# Microcontroller_schematic.net
KiCad netlist of a schematic drawn in Altium Designer
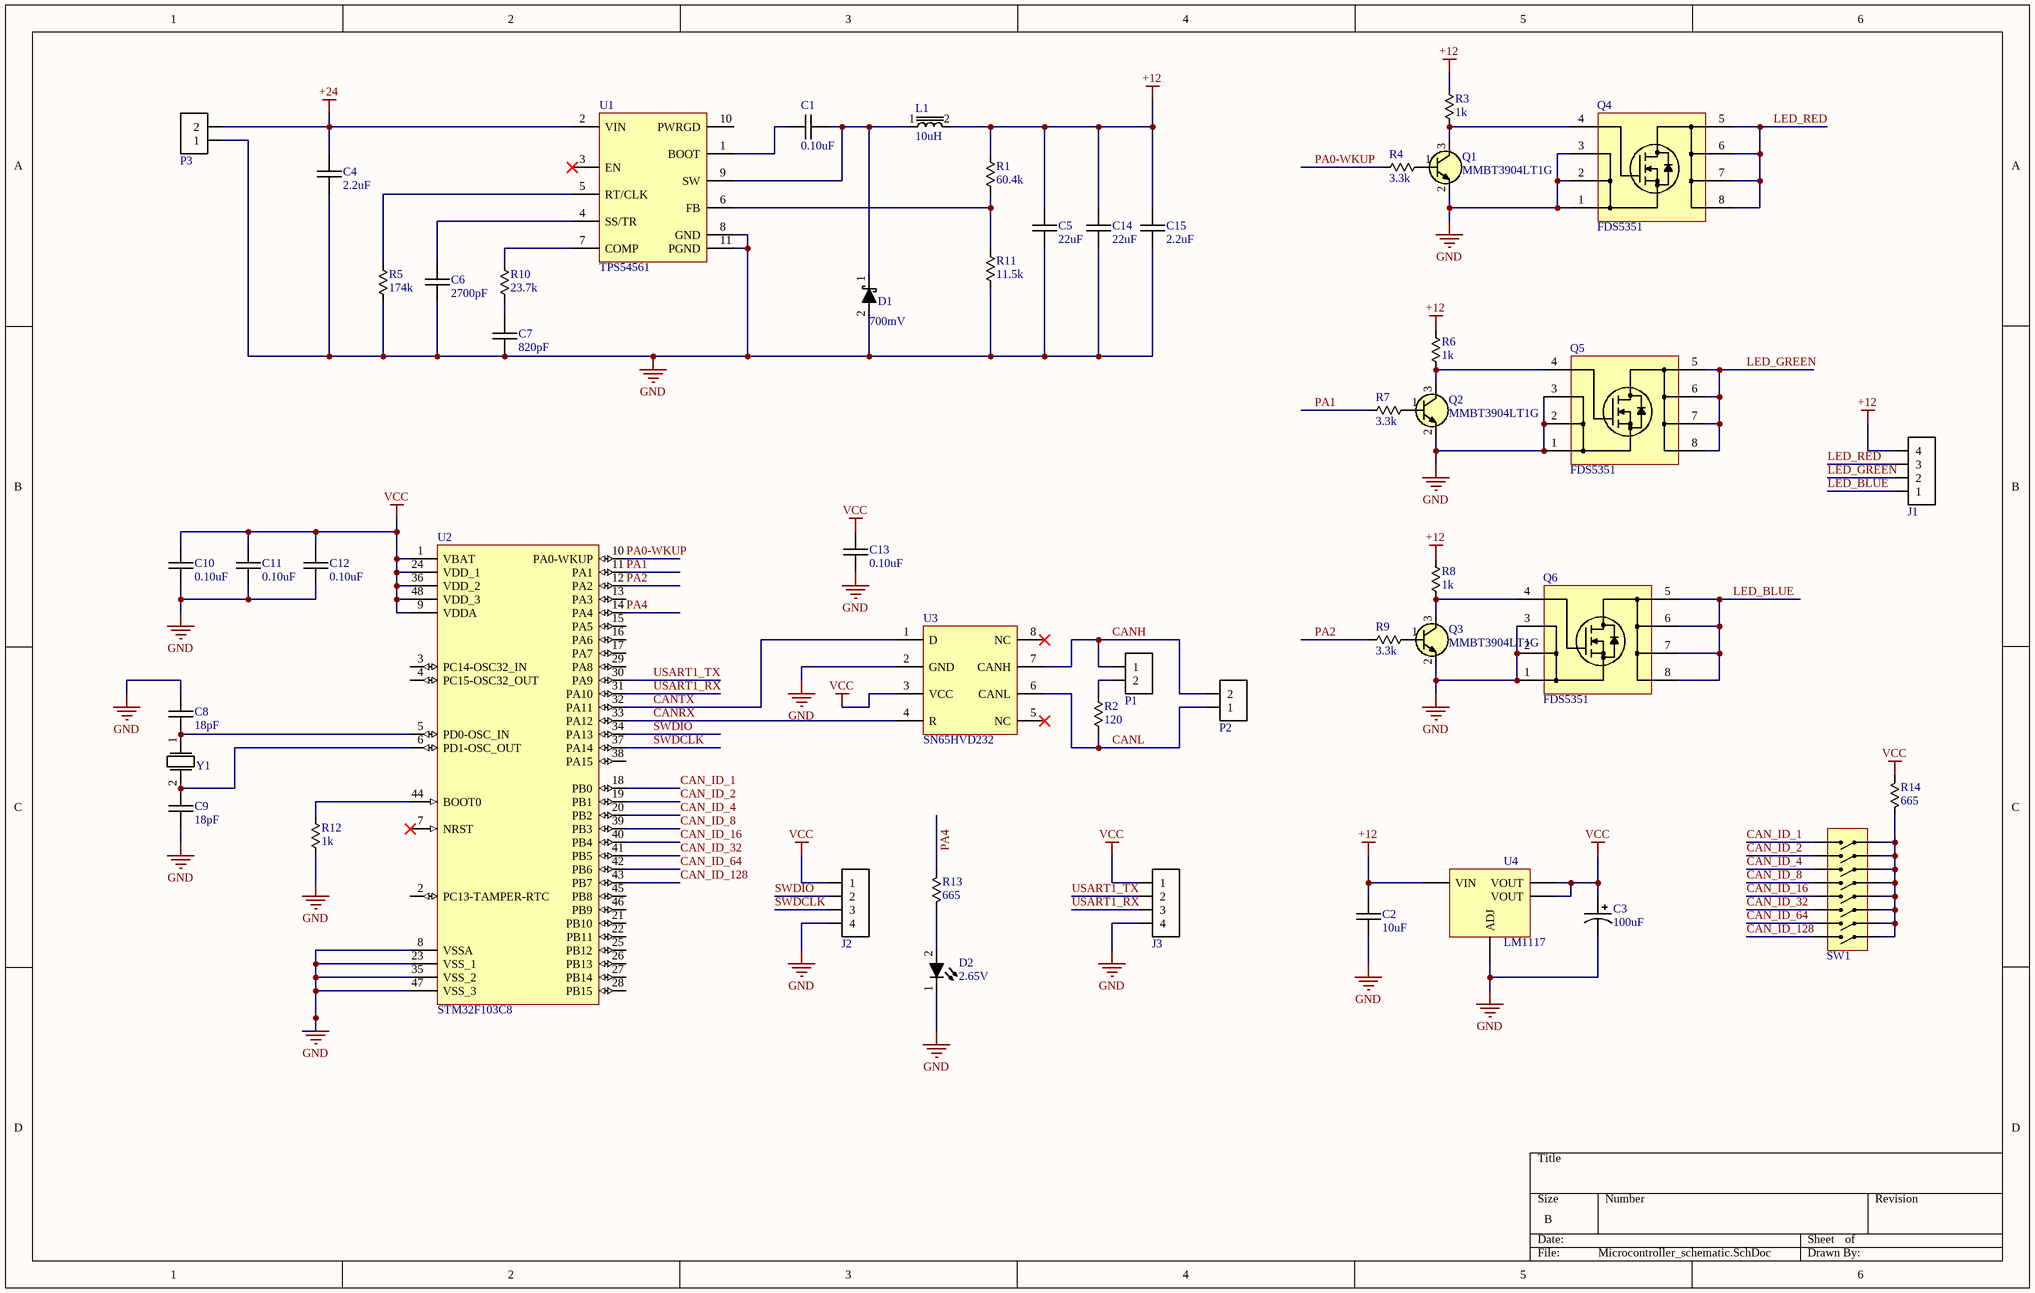
[diagram p0: Microcontroller_schematic.SchDoc]

(export (version "E")
  (design (tool "Eeschema 10.0.6"))
  (components
    (comp (ref "C1")
      (value "0.10uF")
      (footprint "chip_0805")
      (description "CAP, 0.10uF, 10%, 16V, X7R, 0805")
      (fields (field (name "PART NUMBER") "CAP-00069") (field (name "TOLERANCE") "10%"))
      (libsource (lib "Capacitors$") (part "CAP-00069"))
    )
    (comp (ref "C2")
      (value "10uF")
      (footprint "chip_1206")
      (description "CAP, 10uF, ±10%, 25V, X7R, 1206")
      (fields (field (name "PART NUMBER") "CAP-00539") (field (name "TOLERANCE") "±10%"))
      (libsource (lib "Capacitors$") (part "CAP-00539"))
    )
    (comp (ref "C3")
      (value "100uF")
      (footprint "chip_2917_AVX_TAJD")
      (description "CAP, 100uF, ±10%, 16V, Tantalum, 2917")
      (fields (field (name "PART NUMBER") "CAP-00550") (field (name "TOLERANCE") "±10%"))
      (libsource (lib "Capacitors$") (part "CAP-00550"))
    )
    (comp (ref "C4")
      (value "2.2uF")
      (footprint "chip_1206")
      (description "CAP, 2.2uF, ±10%, 50V, X7R, 1206")
      (fields (field (name "PART NUMBER") "CAP-00563") (field (name "TOLERANCE") "±10%"))
      (libsource (lib "Capacitors$") (part "CAP-00563"))
    )
    (comp (ref "C5")
      (value "22uF")
      (footprint "chip_1206")
      (description "CAP, 22uF, ±10%, 25V, X5R, 1206")
      (fields (field (name "PART NUMBER") "CAP-00587") (field (name "TOLERANCE") "±10%"))
      (libsource (lib "Capacitors$") (part "CAP-00587"))
    )
    (comp (ref "C6")
      (value "2700pF")
      (footprint "chip_0805")
      (description "CAP, 2700pF, 10%, 50V, X7R, 0805")
      (fields (field (name "PART NUMBER") "CAP-00024") (field (name "TOLERANCE") "10%"))
      (libsource (lib "Capacitors$") (part "CAP-00024"))
    )
    (comp (ref "C7")
      (value "820pF")
      (footprint "chip_0805")
      (description "CAP, 820pF, 10%, 50V, X7R, 0805")
      (fields (field (name "PART NUMBER") "CAP-00008") (field (name "TOLERANCE") "10%"))
      (libsource (lib "Capacitors$") (part "CAP-00008"))
    )
    (comp (ref "C8")
      (value "18pF")
      (footprint "chip_0603")
      (description "CAP, 18pF, ±2%, 50V, C0G, 0603")
      (fields (field (name "PART NUMBER") "CAP-00409") (field (name "TOLERANCE") "±2%"))
      (libsource (lib "Capacitors$") (part "CAP-00409"))
    )
    (comp (ref "C9")
      (value "18pF")
      (footprint "chip_0603")
      (description "CAP, 18pF, ±2%, 50V, C0G, 0603")
      (fields (field (name "PART NUMBER") "CAP-00409") (field (name "TOLERANCE") "±2%"))
      (libsource (lib "Capacitors$") (part "CAP-00409"))
    )
    (comp (ref "C10")
      (value "0.10uF")
      (footprint "chip_0805")
      (description "CAP, 0.10uF, 10%, 16V, X7R, 0805")
      (fields (field (name "PART NUMBER") "CAP-00069") (field (name "TOLERANCE") "10%"))
      (libsource (lib "Capacitors$") (part "CAP-00069"))
    )
    (comp (ref "C11")
      (value "0.10uF")
      (footprint "chip_0805")
      (description "CAP, 0.10uF, 10%, 16V, X7R, 0805")
      (fields (field (name "PART NUMBER") "CAP-00069") (field (name "TOLERANCE") "10%"))
      (libsource (lib "Capacitors$") (part "CAP-00069"))
    )
    (comp (ref "C12")
      (value "0.10uF")
      (footprint "chip_0805")
      (description "CAP, 0.10uF, 10%, 16V, X7R, 0805")
      (fields (field (name "PART NUMBER") "CAP-00069") (field (name "TOLERANCE") "10%"))
      (libsource (lib "Capacitors$") (part "CAP-00069"))
    )
    (comp (ref "C13")
      (value "0.10uF")
      (footprint "chip_0805")
      (description "CAP, 0.10uF, 10%, 16V, X7R, 0805")
      (fields (field (name "PART NUMBER") "CAP-00069") (field (name "TOLERANCE") "10%"))
      (libsource (lib "Capacitors$") (part "CAP-00069"))
    )
    (comp (ref "C14")
      (value "22uF")
      (footprint "chip_1206")
      (description "CAP, 22uF, ±10%, 25V, X5R, 1206")
      (fields (field (name "PART NUMBER") "CAP-00587") (field (name "TOLERANCE") "±10%"))
      (libsource (lib "Capacitors$") (part "CAP-00587"))
    )
    (comp (ref "C15")
      (value "2.2uF")
      (footprint "chip_1206")
      (description "CAP, 2.2uF, ±10%, 50V, X7R, 1206")
      (fields (field (name "PART NUMBER") "CAP-00563") (field (name "TOLERANCE") "±10%"))
      (libsource (lib "Capacitors$") (part "CAP-00563"))
    )
    (comp (ref "D1")
      (value "700mV")
      (footprint "do-214ab")
      (description "Dio, Schottky, 5A, 700mV, 60V, SMC")
      (fields (field (name "PART NUMBER") "DIO-00048") (field (name "MANUFACTURER") "Diodes Incorporated"))
      (libsource (lib "Diodes$") (part "DIO-00048"))
    )
    (comp (ref "D2")
      (value "2.65V")
      (footprint "chip_0603_LED")
      (description "LED, Green, 0603, Low current, HELI2 Series")
      (fields (field (name "PART NUMBER") "DIO-00050") (field (name "MANUFACTURER") "Kingbright"))
      (libsource (lib "Diodes$") (part "DIO-00050"))
    )
    (comp (ref "J1")
      (value "conn-4x1_0")
      (footprint "TERM_3.50MM_4x1_0")
      (description "Term Blk, 4 Pos, 8A, 3.5mm Pitch, Screwless")
      (fields (field (name "PART NUMBER") "CONN-00024") (field (name "MANUFACTURER") "Phoenix Contact"))
      (libsource (lib "Connectors$") (part "CONN-00024"))
    )
    (comp (ref "J2")
      (value "conn-4x1_0")
      (footprint "HDDR_4x1_0")
      (description "Header 4x1, 0.1\"")
      (fields (field (name "PART NUMBER") "CONN-00029"))
      (libsource (lib "Connectors$") (part "CONN-00029"))
    )
    (comp (ref "J3")
      (value "conn-4x1_0")
      (footprint "HDDR_4x1_0")
      (description "Header 4x1, 0.1\"")
      (fields (field (name "PART NUMBER") "CONN-00029"))
      (libsource (lib "Connectors$") (part "CONN-00029"))
    )
    (comp (ref "L1")
      (value "ind_1")
      (footprint "VISHAY_IHLP3232DZ")
      (description "Ind, 10uH, 20%, 5.2A (9A sat.), 0.0599 Ohm")
      (fields
        (field (name "PART NUMBER") "MAG-00106")
        (field (name "INDUCTANCE") "10uH")
        (field (name "TOLERANCE") "20%")
      )
      (libsource (lib "Magnetics$") (part "MAG-00106"))
    )
    (comp (ref "P1")
      (value "conn-2x1_0")
      (footprint "HDDR_2x1_0")
      (description "Header, 2x1, 0.1\"")
      (fields (field (name "PART NUMBER") "CONN-00055") (field (name "MANUFACTURER") "Samtec"))
      (libsource (lib "Connectors$") (part "CONN-00055"))
    )
    (comp (ref "P2")
      (value "conn-2x1_0")
      (footprint "TERM_3.50MM_2x1_0")
      (description "Term Blk, 2 Pos, 8A, 3.5mm Pitch, Screwless")
      (fields (field (name "PART NUMBER") "CONN-00023") (field (name "MANUFACTURER") "Phoenix Contact"))
      (libsource (lib "Connectors$") (part "CONN-00023"))
    )
    (comp (ref "P3")
      (value "conn-2x1_0")
      (footprint "TERM_3.50MM_2x1_0")
      (description "Term Blk, 2 Pos, 8A, 3.5mm Pitch, Screwless")
      (fields (field (name "PART NUMBER") "CONN-00023") (field (name "MANUFACTURER") "Phoenix Contact"))
      (libsource (lib "Connectors$") (part "CONN-00023"))
    )
    (comp (ref "Q1")
      (value "MMBT3904LT1G")
      (footprint "SOT-23-3_1")
      (description "XSTR, NPN, 200mA, 40V, Vce 0.3V, SOT-23-3")
      (fields (field (name "PART NUMBER") "XSTR-00037") (field (name "MANUFACTURER") "ON Semi"))
      (libsource (lib "Transistors$") (part "XSTR-00037"))
    )
    (comp (ref "Q2")
      (value "MMBT3904LT1G")
      (footprint "SOT-23-3_1")
      (description "XSTR, NPN, 200mA, 40V, Vce 0.3V, SOT-23-3")
      (fields (field (name "PART NUMBER") "XSTR-00037") (field (name "MANUFACTURER") "ON Semi"))
      (libsource (lib "Transistors$") (part "XSTR-00037"))
    )
    (comp (ref "Q3")
      (value "MMBT3904LT1G")
      (footprint "SOT-23-3_1")
      (description "XSTR, NPN, 200mA, 40V, Vce 0.3V, SOT-23-3")
      (fields (field (name "PART NUMBER") "XSTR-00037") (field (name "MANUFACTURER") "ON Semi"))
      (libsource (lib "Transistors$") (part "XSTR-00037"))
    )
    (comp (ref "Q4")
      (value "FDS5351")
      (footprint "SO-8")
      (description "XSTR NFET, 6.1A, 60V, 5W, SOIC-8")
      (fields (field (name "PART NUMBER") "XSTR-00034") (field (name "MANUFACTURER") "ON Semi"))
      (libsource (lib "Transistors$") (part "XSTR-00034"))
    )
    (comp (ref "Q5")
      (value "FDS5351")
      (footprint "SO-8")
      (description "XSTR NFET, 6.1A, 60V, 5W, SOIC-8")
      (fields (field (name "PART NUMBER") "XSTR-00034") (field (name "MANUFACTURER") "ON Semi"))
      (libsource (lib "Transistors$") (part "XSTR-00034"))
    )
    (comp (ref "Q6")
      (value "FDS5351")
      (footprint "SO-8")
      (description "XSTR NFET, 6.1A, 60V, 5W, SOIC-8")
      (fields (field (name "PART NUMBER") "XSTR-00034") (field (name "MANUFACTURER") "ON Semi"))
      (libsource (lib "Transistors$") (part "XSTR-00034"))
    )
    (comp (ref "R1")
      (value "60.4k")
      (footprint "chip_0805")
      (description "RES SMD 60.4K OHM 1% 1/8W 0805")
      (fields (field (name "PART NUMBER") "RES-00531") (field (name "TOLERANCE") "1%"))
      (libsource (lib "Resistors$") (part "RES-00531"))
    )
    (comp (ref "R2")
      (value "120")
      (footprint "chip_0805")
      (description "RES SMD 120 OHM 1% 1/8W 0805")
      (fields (field (name "PART NUMBER") "RES-00183") (field (name "TOLERANCE") "1%"))
      (libsource (lib "Resistors$") (part "RES-00183"))
    )
    (comp (ref "R3")
      (value "1k")
      (footprint "chip_0805")
      (description "RES SMD 1K OHM 1% 1/8W 0805")
      (fields (field (name "PART NUMBER") "RES-00361") (field (name "TOLERANCE") "1%"))
      (libsource (lib "Resistors$") (part "RES-00361"))
    )
    (comp (ref "R4")
      (value "3.3k")
      (footprint "chip_0603")
      (description "RES SMD 3.3K OHM 1% 1/4W 0603")
      (fields (field (name "PART NUMBER") "RES-00419") (field (name "TOLERANCE") "1%"))
      (libsource (lib "Resistors$") (part "RES-00419"))
    )
    (comp (ref "R5")
      (value "174k")
      (footprint "chip_0805")
      (description "RES SMD 174K OHM 1% 1/8W 0805")
      (fields (field (name "PART NUMBER") "RES-00350") (field (name "TOLERANCE") "1%"))
      (libsource (lib "Resistors$") (part "RES-00350"))
    )
    (comp (ref "R6")
      (value "1k")
      (footprint "chip_0805")
      (description "RES SMD 1K OHM 1% 1/8W 0805")
      (fields (field (name "PART NUMBER") "RES-00361") (field (name "TOLERANCE") "1%"))
      (libsource (lib "Resistors$") (part "RES-00361"))
    )
    (comp (ref "R7")
      (value "3.3k")
      (footprint "chip_0603")
      (description "RES SMD 3.3K OHM 1% 1/4W 0603")
      (fields (field (name "PART NUMBER") "RES-00419") (field (name "TOLERANCE") "1%"))
      (libsource (lib "Resistors$") (part "RES-00419"))
    )
    (comp (ref "R8")
      (value "1k")
      (footprint "chip_0805")
      (description "RES SMD 1K OHM 1% 1/8W 0805")
      (fields (field (name "PART NUMBER") "RES-00361") (field (name "TOLERANCE") "1%"))
      (libsource (lib "Resistors$") (part "RES-00361"))
    )
    (comp (ref "R9")
      (value "3.3k")
      (footprint "chip_0603")
      (description "RES SMD 3.3K OHM 1% 1/4W 0603")
      (fields (field (name "PART NUMBER") "RES-00419") (field (name "TOLERANCE") "1%"))
      (libsource (lib "Resistors$") (part "RES-00419"))
    )
    (comp (ref "R10")
      (value "23.7k")
      (footprint "chip_0805")
      (description "RES SMD 23.7K OHM 1% 1/8W 0805")
      (fields (field (name "PART NUMBER") "RES-00392") (field (name "TOLERANCE") "1%"))
      (libsource (lib "Resistors$") (part "RES-00392"))
    )
    (comp (ref "R11")
      (value "11.5k")
      (footprint "chip_0805")
      (description "RES SMD 11.5K OHM 1% 1/8W 0805")
      (fields (field (name "PART NUMBER") "RES-00309") (field (name "TOLERANCE") "1%"))
      (libsource (lib "Resistors$") (part "RES-00309"))
    )
    (comp (ref "R12")
      (value "1k")
      (footprint "chip_0805")
      (description "RES SMD 1K OHM 1% 1/8W 0805")
      (fields (field (name "PART NUMBER") "RES-00361") (field (name "TOLERANCE") "1%"))
      (libsource (lib "Resistors$") (part "RES-00361"))
    )
    (comp (ref "R13")
      (value "665")
      (footprint "chip_0805")
      (description "RES SMD 665 OHM 1% 1/8W 0805")
      (fields (field (name "PART NUMBER") "RES-00248") (field (name "TOLERANCE") "1%"))
      (libsource (lib "Resistors$") (part "RES-00248"))
    )
    (comp (ref "R14")
      (value "665")
      (footprint "chip_0805")
      (description "RES SMD 665 OHM 1% 1/8W 0805")
      (fields (field (name "PART NUMBER") "RES-00248") (field (name "TOLERANCE") "1%"))
      (libsource (lib "Resistors$") (part "RES-00248"))
    )
    (comp (ref "SW1")
      (value "DIP_SW_8")
      (footprint "A6S-8104-H")
      (description "DIP Switch, 8 Switches, SMD, 25mA, 24V")
      (fields (field (name "PART NUMBER") "MISC-00045") (field (name "MANUFACTURER") "Omron"))
      (libsource (lib "Misc$") (part "MISC-00045"))
    )
    (comp (ref "U1")
      (value "TPS54561")
      (footprint "WSON-10_0")
      (description "REG, SW Buck Adj, 5A, 4.5-60V, 2.5MHz, TPS54561")
      (fields (field (name "PART NUMBER") "PWREG-00033") (field (name "MANUFACTURER") "TI"))
      (libsource (lib "Power Reg$") (part "PWREG-00033"))
    )
    (comp (ref "U2")
      (value "STM32F103C8")
      (footprint "LQFP48_0")
      (description "STM32 M3, LQFP-48")
      (fields (field (name "PART NUMBER") "UCTRL-00008") (field (name "MANUFACTURER") "ST"))
      (libsource (lib "Microcontrollers$") (part "UCTRL-00008"))
    )
    (comp (ref "U3")
      (value "SN65HVD232")
      (footprint "SO-8")
      (description "CANbus Transceiver, Single channel, SN65HVD232")
      (fields (field (name "PART NUMBER") "IFACE-00008") (field (name "MANUFACTURER") "TI"))
      (libsource (lib "Interfaces$") (part "IFACE-00008"))
    )
    (comp (ref "U4")
      (value "LM1117")
      (footprint "sot-223-4")
      (description "REG, Linear, Fixed 3V3, 800mA, SOT-223")
      (fields (field (name "PART NUMBER") "PWREG-00018") (field (name "MANUFACTURER") "TI"))
      (libsource (lib "Power Reg$") (part "PWREG-00018"))
    )
    (comp (ref "Y1")
      (value "osc_xtal_2p_0")
      (footprint "ABLS_AT49_OSC")
      (description "XTAL, 8MHz, 18pF, 20ppm")
      (fields (field (name "PART NUMBER") "OSC-00002") (field (name "TOLERANCE") "20ppm"))
      (libsource (lib "Oscillators$") (part "OSC-00002"))
    )
  )
  (nets
    (net (code "1") (name "+12") (class "Default")
      (node (ref "C14") (pin "1") (pinfunction "1_1") (pintype "passive"))
      (node (ref "C15") (pin "1") (pinfunction "1_1") (pintype "passive"))
      (node (ref "C2") (pin "1") (pinfunction "1_1") (pintype "passive"))
      (node (ref "C5") (pin "1") (pinfunction "1_1") (pintype "passive"))
      (node (ref "J1") (pin "4") (pinfunction "4_4") (pintype "passive"))
      (node (ref "L1") (pin "2") (pinfunction "2_2") (pintype "passive"))
      (node (ref "R1") (pin "1") (pinfunction "1_1") (pintype "passive"))
      (node (ref "R3") (pin "1") (pinfunction "1_1") (pintype "passive"))
      (node (ref "R6") (pin "1") (pinfunction "1_1") (pintype "passive"))
      (node (ref "R8") (pin "1") (pinfunction "1_1") (pintype "passive"))
      (node (ref "U4") (pin "3") (pinfunction "VIN_3") (pintype "passive"))
    )
    (net (code "2") (name "+24") (class "Default")
      (node (ref "C4") (pin "1") (pinfunction "1_1") (pintype "passive"))
      (node (ref "P3") (pin "2") (pinfunction "2_2") (pintype "passive"))
      (node (ref "U1") (pin "2") (pinfunction "VIN_2") (pintype "passive"))
    )
    (net (code "3") (name "/CANH") (class "Default")
      (node (ref "P1") (pin "1") (pinfunction "1_1") (pintype "passive"))
      (node (ref "P2") (pin "2") (pinfunction "2_2") (pintype "passive"))
      (node (ref "U3") (pin "7") (pinfunction "CANH_7") (pintype "passive"))
    )
    (net (code "4") (name "/CANL") (class "Default")
      (node (ref "P2") (pin "1") (pinfunction "1_1") (pintype "passive"))
      (node (ref "R2") (pin "2") (pinfunction "2_2") (pintype "passive"))
      (node (ref "U3") (pin "6") (pinfunction "CANL_6") (pintype "passive"))
    )
    (net (code "5") (name "/CANRX") (class "Default")
      (node (ref "U2") (pin "33") (pinfunction "PA12_33") (pintype "bidirectional"))
      (node (ref "U3") (pin "4") (pinfunction "R_4") (pintype "passive"))
    )
    (net (code "6") (name "/CANTX") (class "Default")
      (node (ref "U2") (pin "32") (pinfunction "PA11_32") (pintype "bidirectional"))
      (node (ref "U3") (pin "1") (pinfunction "D_1") (pintype "passive"))
    )
    (net (code "7") (name "/CAN_ID_1") (class "Default")
      (node (ref "SW1") (pin "9") (pinfunction "9_9") (pintype "passive"))
      (node (ref "U2") (pin "18") (pinfunction "PB0_18") (pintype "bidirectional"))
    )
    (net (code "8") (name "/CAN_ID_2") (class "Default")
      (node (ref "SW1") (pin "10") (pinfunction "10_10") (pintype "passive"))
      (node (ref "U2") (pin "19") (pinfunction "PB1_19") (pintype "bidirectional"))
    )
    (net (code "9") (name "/CAN_ID_4") (class "Default")
      (node (ref "SW1") (pin "11") (pinfunction "11_11") (pintype "passive"))
      (node (ref "U2") (pin "20") (pinfunction "PB2_20") (pintype "bidirectional"))
    )
    (net (code "10") (name "/CAN_ID_8") (class "Default")
      (node (ref "SW1") (pin "12") (pinfunction "12_12") (pintype "passive"))
      (node (ref "U2") (pin "39") (pinfunction "PB3_39") (pintype "bidirectional"))
    )
    (net (code "11") (name "/CAN_ID_16") (class "Default")
      (node (ref "SW1") (pin "13") (pinfunction "13_13") (pintype "passive"))
      (node (ref "U2") (pin "40") (pinfunction "PB4_40") (pintype "bidirectional"))
    )
    (net (code "12") (name "/CAN_ID_32") (class "Default")
      (node (ref "SW1") (pin "14") (pinfunction "14_14") (pintype "passive"))
      (node (ref "U2") (pin "41") (pinfunction "PB5_41") (pintype "bidirectional"))
    )
    (net (code "13") (name "/CAN_ID_64") (class "Default")
      (node (ref "SW1") (pin "15") (pinfunction "15_15") (pintype "passive"))
      (node (ref "U2") (pin "42") (pinfunction "PB6_42") (pintype "bidirectional"))
    )
    (net (code "14") (name "/CAN_ID_128") (class "Default")
      (node (ref "SW1") (pin "16") (pinfunction "16_16") (pintype "passive"))
      (node (ref "U2") (pin "43") (pinfunction "PB7_43") (pintype "bidirectional"))
    )
    (net (code "15") (name "/LED_BLUE") (class "Default")
      (node (ref "J1") (pin "1") (pinfunction "1_1") (pintype "passive"))
      (node (ref "Q6") (pin "5") (pinfunction "D_5") (pintype "passive"))
      (node (ref "Q6") (pin "6") (pinfunction "D_6") (pintype "passive"))
      (node (ref "Q6") (pin "7") (pinfunction "D_7") (pintype "passive"))
      (node (ref "Q6") (pin "8") (pinfunction "D_8") (pintype "passive"))
    )
    (net (code "16") (name "/LED_GREEN") (class "Default")
      (node (ref "J1") (pin "2") (pinfunction "2_2") (pintype "passive"))
      (node (ref "Q5") (pin "5") (pinfunction "D_5") (pintype "passive"))
      (node (ref "Q5") (pin "6") (pinfunction "D_6") (pintype "passive"))
      (node (ref "Q5") (pin "7") (pinfunction "D_7") (pintype "passive"))
      (node (ref "Q5") (pin "8") (pinfunction "D_8") (pintype "passive"))
    )
    (net (code "17") (name "/LED_RED") (class "Default")
      (node (ref "J1") (pin "3") (pinfunction "3_3") (pintype "passive"))
      (node (ref "Q4") (pin "5") (pinfunction "D_5") (pintype "passive"))
      (node (ref "Q4") (pin "6") (pinfunction "D_6") (pintype "passive"))
      (node (ref "Q4") (pin "7") (pinfunction "D_7") (pintype "passive"))
      (node (ref "Q4") (pin "8") (pinfunction "D_8") (pintype "passive"))
    )
    (net (code "18") (name "/PA0-WKUP") (class "Default")
      (node (ref "R4") (pin "2") (pinfunction "2_2") (pintype "passive"))
      (node (ref "U2") (pin "10") (pinfunction "PA0-WKUP_10") (pintype "bidirectional"))
    )
    (net (code "19") (name "/PA1") (class "Default")
      (node (ref "R7") (pin "2") (pinfunction "2_2") (pintype "passive"))
      (node (ref "U2") (pin "11") (pinfunction "PA1_11") (pintype "bidirectional"))
    )
    (net (code "20") (name "/PA2") (class "Default")
      (node (ref "R9") (pin "2") (pinfunction "2_2") (pintype "passive"))
      (node (ref "U2") (pin "12") (pinfunction "PA2_12") (pintype "bidirectional"))
    )
    (net (code "21") (name "/PA4") (class "Default")
      (node (ref "R13") (pin "2") (pinfunction "2_2") (pintype "passive"))
      (node (ref "U2") (pin "14") (pinfunction "PA4_14") (pintype "bidirectional"))
    )
    (net (code "22") (name "/SWDCLK") (class "Default")
      (node (ref "J2") (pin "3") (pinfunction "3_3") (pintype "passive"))
      (node (ref "U2") (pin "37") (pinfunction "PA14_37") (pintype "bidirectional"))
    )
    (net (code "23") (name "/SWDIO") (class "Default")
      (node (ref "J2") (pin "2") (pinfunction "2_2") (pintype "passive"))
      (node (ref "U2") (pin "34") (pinfunction "PA13_34") (pintype "bidirectional"))
    )
    (net (code "24") (name "/USART1_RX") (class "Default")
      (node (ref "J3") (pin "3") (pinfunction "3_3") (pintype "passive"))
      (node (ref "U2") (pin "31") (pinfunction "PA10_31") (pintype "bidirectional"))
    )
    (net (code "25") (name "/USART1_TX") (class "Default")
      (node (ref "J3") (pin "2") (pinfunction "2_2") (pintype "passive"))
      (node (ref "U2") (pin "30") (pinfunction "PA9_30") (pintype "bidirectional"))
    )
    (net (code "26") (name "GND") (class "Default")
      (node (ref "C10") (pin "1") (pinfunction "1_1") (pintype "passive"))
      (node (ref "C11") (pin "2") (pinfunction "2_2") (pintype "passive"))
      (node (ref "C12") (pin "1") (pinfunction "1_1") (pintype "passive"))
      (node (ref "C13") (pin "1") (pinfunction "1_1") (pintype "passive"))
      (node (ref "C14") (pin "2") (pinfunction "2_2") (pintype "passive"))
      (node (ref "C15") (pin "2") (pinfunction "2_2") (pintype "passive"))
      (node (ref "C2") (pin "2") (pinfunction "2_2") (pintype "passive"))
      (node (ref "C3") (pin "2") (pinfunction "2_2") (pintype "passive"))
      (node (ref "C4") (pin "2") (pinfunction "2_2") (pintype "passive"))
      (node (ref "C5") (pin "2") (pinfunction "2_2") (pintype "passive"))
      (node (ref "C6") (pin "2") (pinfunction "2_2") (pintype "passive"))
      (node (ref "C7") (pin "2") (pinfunction "2_2") (pintype "passive"))
      (node (ref "C8") (pin "1") (pinfunction "1_1") (pintype "passive"))
      (node (ref "C9") (pin "2") (pinfunction "2_2") (pintype "passive"))
      (node (ref "D1") (pin "2") (pinfunction "2_2") (pintype "passive"))
      (node (ref "D2") (pin "1") (pinfunction "1_1") (pintype "passive"))
      (node (ref "J2") (pin "4") (pinfunction "4_4") (pintype "passive"))
      (node (ref "J3") (pin "4") (pinfunction "4_4") (pintype "passive"))
      (node (ref "P3") (pin "1") (pinfunction "1_1") (pintype "passive"))
      (node (ref "Q1") (pin "2") (pinfunction "E_2") (pintype "passive"))
      (node (ref "Q2") (pin "2") (pinfunction "E_2") (pintype "passive"))
      (node (ref "Q3") (pin "2") (pinfunction "E_2") (pintype "passive"))
      (node (ref "Q4") (pin "1") (pinfunction "S_1") (pintype "passive"))
      (node (ref "Q4") (pin "2") (pinfunction "S_2") (pintype "passive"))
      (node (ref "Q4") (pin "3") (pinfunction "S_3") (pintype "passive"))
      (node (ref "Q5") (pin "1") (pinfunction "S_1") (pintype "passive"))
      (node (ref "Q5") (pin "2") (pinfunction "S_2") (pintype "passive"))
      (node (ref "Q5") (pin "3") (pinfunction "S_3") (pintype "passive"))
      (node (ref "Q6") (pin "1") (pinfunction "S_1") (pintype "passive"))
      (node (ref "Q6") (pin "2") (pinfunction "S_2") (pintype "passive"))
      (node (ref "Q6") (pin "3") (pinfunction "S_3") (pintype "passive"))
      (node (ref "R11") (pin "2") (pinfunction "2_2") (pintype "passive"))
      (node (ref "R12") (pin "2") (pinfunction "2_2") (pintype "passive"))
      (node (ref "R5") (pin "2") (pinfunction "2_2") (pintype "passive"))
      (node (ref "U1") (pin "11") (pinfunction "PGND_11") (pintype "passive"))
      (node (ref "U1") (pin "8") (pinfunction "GND_8") (pintype "passive"))
      (node (ref "U2") (pin "23") (pinfunction "VSS_1_23") (pintype "power_in"))
      (node (ref "U2") (pin "35") (pinfunction "VSS_2_35") (pintype "power_in"))
      (node (ref "U2") (pin "47") (pinfunction "VSS_3_47") (pintype "power_in"))
      (node (ref "U2") (pin "8") (pinfunction "VSSA_8") (pintype "power_in"))
      (node (ref "U3") (pin "2") (pinfunction "GND_2") (pintype "passive"))
      (node (ref "U4") (pin "1") (pinfunction "ADJ_1") (pintype "passive"))
    )
    (net (code "27") (name "Net-(C7-Pad1)") (class "Default")
      (node (ref "C7") (pin "1") (pinfunction "1_1") (pintype "passive"))
      (node (ref "R10") (pin "2") (pinfunction "2_2") (pintype "passive"))
    )
    (net (code "28") (name "Net-(D2-Pad2)") (class "Default")
      (node (ref "D2") (pin "2") (pinfunction "2_2") (pintype "passive"))
      (node (ref "R13") (pin "1") (pinfunction "1_1") (pintype "passive"))
    )
    (net (code "29") (name "Net-(P1-Pad2)") (class "Default")
      (node (ref "P1") (pin "2") (pinfunction "2_2") (pintype "passive"))
      (node (ref "R2") (pin "1") (pinfunction "1_1") (pintype "passive"))
    )
    (net (code "30") (name "Net-(Q1-B)") (class "Default")
      (node (ref "Q1") (pin "1") (pinfunction "B_1") (pintype "passive"))
      (node (ref "R4") (pin "1") (pinfunction "1_1") (pintype "passive"))
    )
    (net (code "31") (name "Net-(Q1-C)") (class "Default")
      (node (ref "Q1") (pin "3") (pinfunction "C_3") (pintype "passive"))
      (node (ref "Q4") (pin "4") (pinfunction "G_4") (pintype "passive"))
      (node (ref "R3") (pin "2") (pinfunction "2_2") (pintype "passive"))
    )
    (net (code "32") (name "Net-(Q2-B)") (class "Default")
      (node (ref "Q2") (pin "1") (pinfunction "B_1") (pintype "passive"))
      (node (ref "R7") (pin "1") (pinfunction "1_1") (pintype "passive"))
    )
    (net (code "33") (name "Net-(Q2-C)") (class "Default")
      (node (ref "Q2") (pin "3") (pinfunction "C_3") (pintype "passive"))
      (node (ref "Q5") (pin "4") (pinfunction "G_4") (pintype "passive"))
      (node (ref "R6") (pin "2") (pinfunction "2_2") (pintype "passive"))
    )
    (net (code "34") (name "Net-(Q3-B)") (class "Default")
      (node (ref "Q3") (pin "1") (pinfunction "B_1") (pintype "passive"))
      (node (ref "R9") (pin "1") (pinfunction "1_1") (pintype "passive"))
    )
    (net (code "35") (name "Net-(Q3-C)") (class "Default")
      (node (ref "Q3") (pin "3") (pinfunction "C_3") (pintype "passive"))
      (node (ref "Q6") (pin "4") (pinfunction "G_4") (pintype "passive"))
      (node (ref "R8") (pin "2") (pinfunction "2_2") (pintype "passive"))
    )
    (net (code "36") (name "Net-(R14-Pad1)") (class "Default")
      (node (ref "R14") (pin "1") (pinfunction "1_1") (pintype "passive"))
      (node (ref "SW1") (pin "1") (pinfunction "1_1") (pintype "passive"))
      (node (ref "SW1") (pin "2") (pinfunction "2_2") (pintype "passive"))
      (node (ref "SW1") (pin "3") (pinfunction "3_3") (pintype "passive"))
      (node (ref "SW1") (pin "4") (pinfunction "4_4") (pintype "passive"))
      (node (ref "SW1") (pin "5") (pinfunction "5_5") (pintype "passive"))
      (node (ref "SW1") (pin "6") (pinfunction "6_6") (pintype "passive"))
      (node (ref "SW1") (pin "7") (pinfunction "7_7") (pintype "passive"))
      (node (ref "SW1") (pin "8") (pinfunction "8_8") (pintype "passive"))
    )
    (net (code "37") (name "Net-(U1-BOOT)") (class "Default")
      (node (ref "C1") (pin "2") (pinfunction "2_2") (pintype "passive"))
      (node (ref "U1") (pin "1") (pinfunction "BOOT_1") (pintype "passive"))
    )
    (net (code "38") (name "Net-(U1-COMP)") (class "Default")
      (node (ref "R10") (pin "1") (pinfunction "1_1") (pintype "passive"))
      (node (ref "U1") (pin "7") (pinfunction "COMP_7") (pintype "passive"))
    )
    (net (code "39") (name "Net-(U1-FB)") (class "Default")
      (node (ref "R1") (pin "2") (pinfunction "2_2") (pintype "passive"))
      (node (ref "R11") (pin "1") (pinfunction "1_1") (pintype "passive"))
      (node (ref "U1") (pin "6") (pinfunction "FB_6") (pintype "passive"))
    )
    (net (code "40") (name "Net-(U1-RT{slash}CLK)") (class "Default")
      (node (ref "R5") (pin "1") (pinfunction "1_1") (pintype "passive"))
      (node (ref "U1") (pin "5") (pinfunction "RT/CLK_5") (pintype "passive"))
    )
    (net (code "41") (name "Net-(U1-SS{slash}TR)") (class "Default")
      (node (ref "C6") (pin "1") (pinfunction "1_1") (pintype "passive"))
      (node (ref "U1") (pin "4") (pinfunction "SS/TR_4") (pintype "passive"))
    )
    (net (code "42") (name "Net-(U1-SW)") (class "Default")
      (node (ref "C1") (pin "1") (pinfunction "1_1") (pintype "passive"))
      (node (ref "D1") (pin "1") (pinfunction "1_1") (pintype "passive"))
      (node (ref "L1") (pin "1") (pinfunction "1_1") (pintype "passive"))
      (node (ref "U1") (pin "9") (pinfunction "SW_9") (pintype "passive"))
    )
    (net (code "43") (name "Net-(U2-BOOT0)") (class "Default")
      (node (ref "R12") (pin "1") (pinfunction "1_1") (pintype "passive"))
      (node (ref "U2") (pin "44") (pinfunction "BOOT0_44") (pintype "input"))
    )
    (net (code "44") (name "Net-(U2-PD0-OSC_IN)") (class "Default")
      (node (ref "C8") (pin "2") (pinfunction "2_2") (pintype "passive"))
      (node (ref "U2") (pin "5") (pinfunction "PD0-OSC_IN_5") (pintype "bidirectional"))
      (node (ref "Y1") (pin "1") (pinfunction "20_1") (pintype "passive"))
    )
    (net (code "45") (name "Net-(U2-PD1-OSC_OUT)") (class "Default")
      (node (ref "C9") (pin "1") (pinfunction "1_1") (pintype "passive"))
      (node (ref "U2") (pin "6") (pinfunction "PD1-OSC_OUT_6") (pintype "bidirectional"))
      (node (ref "Y1") (pin "2") (pinfunction "20_2") (pintype "passive"))
    )
    (net (code "46") (name "VCC") (class "Default")
      (node (ref "C10") (pin "2") (pinfunction "2_2") (pintype "passive"))
      (node (ref "C11") (pin "1") (pinfunction "1_1") (pintype "passive"))
      (node (ref "C12") (pin "2") (pinfunction "2_2") (pintype "passive"))
      (node (ref "C13") (pin "2") (pinfunction "2_2") (pintype "passive"))
      (node (ref "C3") (pin "1") (pinfunction "1_1") (pintype "passive"))
      (node (ref "J2") (pin "1") (pinfunction "1_1") (pintype "passive"))
      (node (ref "J3") (pin "1") (pinfunction "1_1") (pintype "passive"))
      (node (ref "R14") (pin "2") (pinfunction "2_2") (pintype "passive"))
      (node (ref "U2") (pin "1") (pinfunction "VBAT_1") (pintype "passive"))
      (node (ref "U2") (pin "24") (pinfunction "VDD_1_24") (pintype "power_in"))
      (node (ref "U2") (pin "36") (pinfunction "VDD_2_36") (pintype "power_in"))
      (node (ref "U2") (pin "48") (pinfunction "VDD_3_48") (pintype "power_in"))
      (node (ref "U2") (pin "9") (pinfunction "VDDA_9") (pintype "power_in"))
      (node (ref "U3") (pin "3") (pinfunction "VCC_3") (pintype "passive"))
      (node (ref "U4") (pin "2") (pinfunction "VOUT_2") (pintype "passive"))
      (node (ref "U4") (pin "4") (pinfunction "VOUT_4") (pintype "passive"))
    )
    (net (code "47") (name "unconnected-(U1-EN-Pad3)") (class "Default")
      (node (ref "U1") (pin "3") (pinfunction "EN_3") (pintype "passive+no_connect"))
    )
    (net (code "48") (name "unconnected-(U1-PWRGD-Pad10)") (class "Default")
      (node (ref "U1") (pin "10") (pinfunction "PWRGD_10") (pintype "passive"))
    )
    (net (code "49") (name "unconnected-(U2-NRST-Pad7)") (class "Default")
      (node (ref "U2") (pin "7") (pinfunction "NRST_7") (pintype "input+no_connect"))
    )
    (net (code "50") (name "unconnected-(U2-PA3-Pad13)") (class "Default")
      (node (ref "U2") (pin "13") (pinfunction "PA3_13") (pintype "bidirectional"))
    )
    (net (code "51") (name "unconnected-(U2-PA5-Pad15)") (class "Default")
      (node (ref "U2") (pin "15") (pinfunction "PA5_15") (pintype "bidirectional"))
    )
    (net (code "52") (name "unconnected-(U2-PA6-Pad16)") (class "Default")
      (node (ref "U2") (pin "16") (pinfunction "PA6_16") (pintype "bidirectional"))
    )
    (net (code "53") (name "unconnected-(U2-PA7-Pad17)") (class "Default")
      (node (ref "U2") (pin "17") (pinfunction "PA7_17") (pintype "bidirectional"))
    )
    (net (code "54") (name "unconnected-(U2-PA8-Pad29)") (class "Default")
      (node (ref "U2") (pin "29") (pinfunction "PA8_29") (pintype "bidirectional"))
    )
    (net (code "55") (name "unconnected-(U2-PA15-Pad38)") (class "Default")
      (node (ref "U2") (pin "38") (pinfunction "PA15_38") (pintype "bidirectional"))
    )
    (net (code "56") (name "unconnected-(U2-PB8-Pad45)") (class "Default")
      (node (ref "U2") (pin "45") (pinfunction "PB8_45") (pintype "bidirectional"))
    )
    (net (code "57") (name "unconnected-(U2-PB9-Pad46)") (class "Default")
      (node (ref "U2") (pin "46") (pinfunction "PB9_46") (pintype "bidirectional"))
    )
    (net (code "58") (name "unconnected-(U2-PB10-Pad21)") (class "Default")
      (node (ref "U2") (pin "21") (pinfunction "PB10_21") (pintype "bidirectional"))
    )
    (net (code "59") (name "unconnected-(U2-PB11-Pad22)") (class "Default")
      (node (ref "U2") (pin "22") (pinfunction "PB11_22") (pintype "bidirectional"))
    )
    (net (code "60") (name "unconnected-(U2-PB12-Pad25)") (class "Default")
      (node (ref "U2") (pin "25") (pinfunction "PB12_25") (pintype "bidirectional"))
    )
    (net (code "61") (name "unconnected-(U2-PB13-Pad26)") (class "Default")
      (node (ref "U2") (pin "26") (pinfunction "PB13_26") (pintype "bidirectional"))
    )
    (net (code "62") (name "unconnected-(U2-PB14-Pad27)") (class "Default")
      (node (ref "U2") (pin "27") (pinfunction "PB14_27") (pintype "bidirectional"))
    )
    (net (code "63") (name "unconnected-(U2-PB15-Pad28)") (class "Default")
      (node (ref "U2") (pin "28") (pinfunction "PB15_28") (pintype "bidirectional"))
    )
    (net (code "64") (name "unconnected-(U2-PC13-TAMPER-RTC-Pad2)") (class "Default")
      (node (ref "U2") (pin "2") (pinfunction "PC13-TAMPER-RTC_2") (pintype "bidirectional"))
    )
    (net (code "65") (name "unconnected-(U2-PC14-OSC32_IN-Pad3)") (class "Default")
      (node (ref "U2") (pin "3") (pinfunction "PC14-OSC32_IN_3") (pintype "bidirectional"))
    )
    (net (code "66") (name "unconnected-(U2-PC15-OSC32_OUT-Pad4)") (class "Default")
      (node (ref "U2") (pin "4") (pinfunction "PC15-OSC32_OUT_4") (pintype "bidirectional"))
    )
    (net (code "67") (name "unconnected-(U3-NC-Pad5)") (class "Default")
      (node (ref "U3") (pin "5") (pinfunction "NC_5") (pintype "passive+no_connect"))
    )
    (net (code "68") (name "unconnected-(U3-NC-Pad8)") (class "Default")
      (node (ref "U3") (pin "8") (pinfunction "NC_8") (pintype "passive+no_connect"))
    )
  )
)
